# PLL.net
KiCad netlist of a schematic drawn in Altium Designer
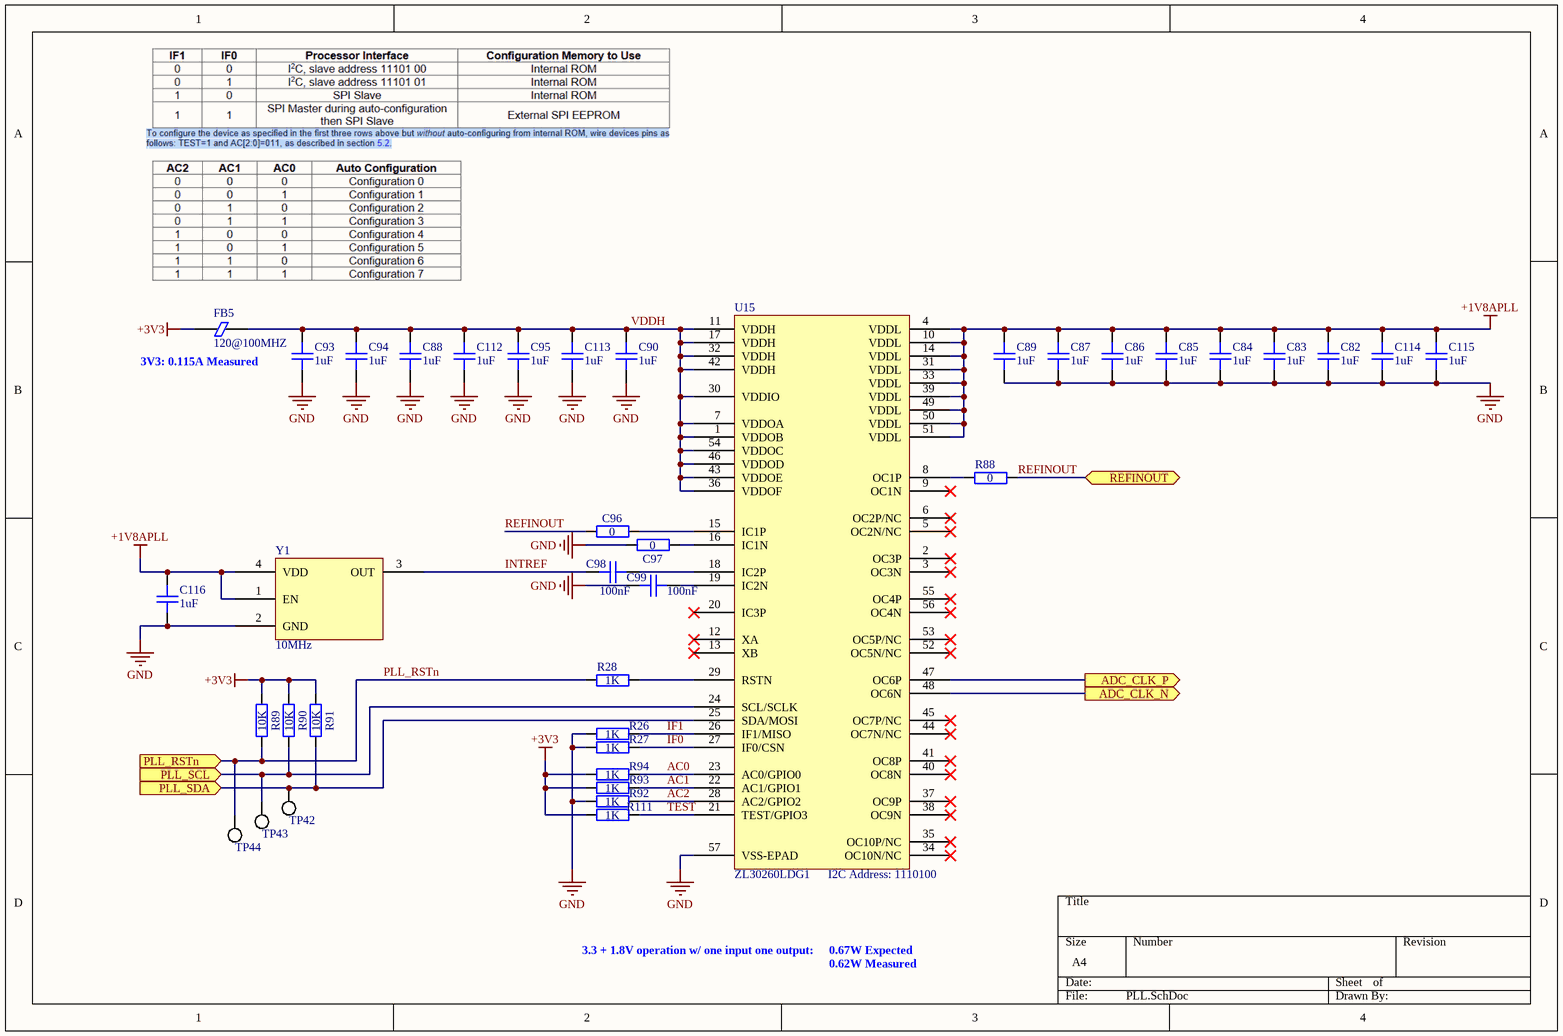
[diagram p0: PLL.SchDoc]

(export (version "E")
  (design (tool "Eeschema 10.0.6"))
  (components
    (comp (ref "C82")
      (value "1uF")
      (footprint "GEN_C_0402")
      (libsource (lib "DSO") (part "CAP 1uF 25V X5R 0402"))
    )
    (comp (ref "C83")
      (value "1uF")
      (footprint "GEN_C_0402")
      (libsource (lib "DSO") (part "CAP 1uF 25V X5R 0402"))
    )
    (comp (ref "C84")
      (value "1uF")
      (footprint "GEN_C_0402")
      (libsource (lib "DSO") (part "CAP 1uF 25V X5R 0402"))
    )
    (comp (ref "C85")
      (value "1uF")
      (footprint "GEN_C_0402")
      (libsource (lib "DSO") (part "CAP 1uF 25V X5R 0402"))
    )
    (comp (ref "C86")
      (value "1uF")
      (footprint "GEN_C_0402")
      (libsource (lib "DSO") (part "CAP 1uF 25V X5R 0402"))
    )
    (comp (ref "C87")
      (value "1uF")
      (footprint "GEN_C_0402")
      (libsource (lib "DSO") (part "CAP 1uF 25V X5R 0402"))
    )
    (comp (ref "C88")
      (value "1uF")
      (footprint "GEN_C_0402")
      (libsource (lib "DSO") (part "CAP 1uF 25V X5R 0402"))
    )
    (comp (ref "C89")
      (value "1uF")
      (footprint "GEN_C_0402")
      (libsource (lib "DSO") (part "CAP 1uF 25V X5R 0402"))
    )
    (comp (ref "C90")
      (value "1uF")
      (footprint "GEN_C_0402")
      (libsource (lib "DSO") (part "CAP 1uF 25V X5R 0402"))
    )
    (comp (ref "C93")
      (value "1uF")
      (footprint "GEN_C_0402")
      (libsource (lib "DSO") (part "CAP 1uF 25V X5R 0402"))
    )
    (comp (ref "C94")
      (value "1uF")
      (footprint "GEN_C_0402")
      (libsource (lib "DSO") (part "CAP 1uF 25V X5R 0402"))
    )
    (comp (ref "C95")
      (value "1uF")
      (footprint "GEN_C_0402")
      (libsource (lib "DSO") (part "CAP 1uF 25V X5R 0402"))
    )
    (comp (ref "C96")
      (value "0")
      (footprint "GEN_R_0402")
      (fields
        (field (name "MANUFACTURER") "Yageo")
        (field (name "MANUFACTURER PART NUMBER") "RC0402JR-070RL")
      )
      (libsource (lib "DSO") (part "RES 0 OHM 1/16W 0402"))
    )
    (comp (ref "C97")
      (value "0")
      (footprint "GEN_R_0402")
      (fields
        (field (name "MANUFACTURER") "Yageo")
        (field (name "MANUFACTURER PART NUMBER") "RC0402JR-070RL")
      )
      (libsource (lib "DSO") (part "RES 0 OHM 1/16W 0402"))
    )
    (comp (ref "C98")
      (value "100nF")
      (footprint "GEN_C_0402")
      (libsource (lib "DSO") (part "CAP 100nF 16V X7R 0402"))
    )
    (comp (ref "C99")
      (value "100nF")
      (footprint "GEN_C_0402")
      (libsource (lib "DSO") (part "CAP 100nF 16V X7R 0402"))
    )
    (comp (ref "C112")
      (value "1uF")
      (footprint "GEN_C_0402")
      (libsource (lib "DSO") (part "CAP 1uF 25V X5R 0402"))
    )
    (comp (ref "C113")
      (value "1uF")
      (footprint "GEN_C_0402")
      (libsource (lib "DSO") (part "CAP 1uF 25V X5R 0402"))
    )
    (comp (ref "C114")
      (value "1uF")
      (footprint "GEN_C_0402")
      (libsource (lib "DSO") (part "CAP 1uF 25V X5R 0402"))
    )
    (comp (ref "C115")
      (value "1uF")
      (footprint "GEN_C_0402")
      (libsource (lib "DSO") (part "CAP 1uF 25V X5R 0402"))
    )
    (comp (ref "C116")
      (value "1uF")
      (footprint "GEN_C_0402")
      (libsource (lib "DSO") (part "CAP 1uF 25V X5R 0402"))
    )
    (comp (ref "FB5")
      (value "120@100MHZ")
      (footprint "GEN_R_0402")
      (libsource (lib "DSO") (part "FERRITE BEAD 120 OHM 0402"))
    )
    (comp (ref "R26")
      (value "1K")
      (footprint "GEN_R_0402")
      (fields
        (field (name "TOLERANCE") "1%")
        (field (name "MANUFACTURER") "Yageo")
        (field (name "HOUSE PART NUMBER") "R-1K-0402-1%-001")
      )
      (libsource (lib "DSO") (part "RES 1K OHM 1% 1/10W 0402"))
    )
    (comp (ref "R27")
      (value "1K")
      (footprint "GEN_R_0402")
      (fields
        (field (name "TOLERANCE") "1%")
        (field (name "MANUFACTURER") "Yageo")
        (field (name "HOUSE PART NUMBER") "R-1K-0402-1%-001")
      )
      (libsource (lib "DSO") (part "RES 1K OHM 1% 1/10W 0402"))
    )
    (comp (ref "R28")
      (value "1K")
      (footprint "GEN_R_0402")
      (fields
        (field (name "TOLERANCE") "1%")
        (field (name "MANUFACTURER") "Yageo")
        (field (name "HOUSE PART NUMBER") "R-1K-0402-1%-001")
      )
      (libsource (lib "") (part "RES 1K OHM 1% 1/10W 0402_1"))
    )
    (comp (ref "R88")
      (value "0")
      (footprint "GEN_R_0402")
      (libsource (lib "") (part "RES 0 OHM 1/16W 0402_1"))
    )
    (comp (ref "R89")
      (value "10K")
      (footprint "GEN_R_0402")
      (fields (field (name "TOLERANCE") "1%"))
      (libsource (lib "DSO") (part "RES 10K OHM 1% 1/10W 0402"))
    )
    (comp (ref "R90")
      (value "10K")
      (footprint "GEN_R_0402")
      (fields (field (name "TOLERANCE") "1%"))
      (libsource (lib "DSO") (part "RES 10K OHM 1% 1/10W 0402"))
    )
    (comp (ref "R91")
      (value "10K")
      (footprint "GEN_R_0402")
      (fields (field (name "TOLERANCE") "1%"))
      (libsource (lib "DSO") (part "RES 10K OHM 1% 1/10W 0402"))
    )
    (comp (ref "R92")
      (value "1K")
      (footprint "GEN_R_0402")
      (fields
        (field (name "TOLERANCE") "1%")
        (field (name "MANUFACTURER") "Yageo")
        (field (name "HOUSE PART NUMBER") "R-1K-0402-1%-001")
      )
      (libsource (lib "DSO") (part "RES 1K OHM 1% 1/10W 0402"))
    )
    (comp (ref "R93")
      (value "1K")
      (footprint "GEN_R_0402")
      (fields
        (field (name "TOLERANCE") "1%")
        (field (name "MANUFACTURER") "Yageo")
        (field (name "HOUSE PART NUMBER") "R-1K-0402-1%-001")
      )
      (libsource (lib "DSO") (part "RES 1K OHM 1% 1/10W 0402"))
    )
    (comp (ref "R94")
      (value "1K")
      (footprint "GEN_R_0402")
      (fields
        (field (name "TOLERANCE") "1%")
        (field (name "MANUFACTURER") "Yageo")
        (field (name "HOUSE PART NUMBER") "R-1K-0402-1%-001")
      )
      (libsource (lib "DSO") (part "RES 1K OHM 1% 1/10W 0402"))
    )
    (comp (ref "R111")
      (value "1K")
      (footprint "GEN_R_0402")
      (fields
        (field (name "TOLERANCE") "1%")
        (field (name "MANUFACTURER") "Yageo")
        (field (name "HOUSE PART NUMBER") "R-1K-0402-1%-001")
      )
      (libsource (lib "DSO") (part "RES 1K OHM 1% 1/10W 0402"))
    )
    (comp (ref "TP42") (value "PCB") (footprint "GEN_TP_PCB") (libsource (lib "DSO") (part "TP PCB 1mm")))
    (comp (ref "TP43") (value "PCB") (footprint "GEN_TP_PCB") (libsource (lib "DSO") (part "TP PCB 1mm")))
    (comp (ref "TP44") (value "PCB") (footprint "GEN_TP_PCB") (libsource (lib "DSO") (part "TP PCB 1mm")))
    (comp (ref "U15")
      (value "ZL30260LDG1")
      (footprint "MC_QFN56_ZL30260")
      (fields (field (name "MANUFACTURER") "Microchip"))
      (libsource (lib "DSO") (part "IC CLK GEN ZL30260LDG1"))
    )
    (comp (ref "Y1")
      (value "10MHz")
      (footprint "ECS_TXO-3225")
      (libsource (lib "DSO") (part "OSC 10MHz ECS-TXO-3225MV"))
    )
  )
  (nets
    (net (code "1") (name "+1V8APLL") (class "Default")
      (node (ref "C114") (pin "1") (pinfunction "1_1") (pintype "passive"))
      (node (ref "C115") (pin "1") (pinfunction "1_1") (pintype "passive"))
      (node (ref "C116") (pin "1") (pinfunction "1_1") (pintype "passive"))
      (node (ref "C82") (pin "1") (pinfunction "1_1") (pintype "passive"))
      (node (ref "C83") (pin "1") (pinfunction "1_1") (pintype "passive"))
      (node (ref "C84") (pin "1") (pinfunction "1_1") (pintype "passive"))
      (node (ref "C85") (pin "1") (pinfunction "1_1") (pintype "passive"))
      (node (ref "C86") (pin "1") (pinfunction "1_1") (pintype "passive"))
      (node (ref "C87") (pin "1") (pinfunction "1_1") (pintype "passive"))
      (node (ref "C89") (pin "1") (pinfunction "1_1") (pintype "passive"))
      (node (ref "U15") (pin "10") (pinfunction "VDDL_10") (pintype "passive"))
      (node (ref "U15") (pin "14") (pinfunction "VDDL_14") (pintype "passive"))
      (node (ref "U15") (pin "31") (pinfunction "VDDL_31") (pintype "passive"))
      (node (ref "U15") (pin "33") (pinfunction "VDDL_33") (pintype "passive"))
      (node (ref "U15") (pin "39") (pinfunction "VDDL_39") (pintype "passive"))
      (node (ref "U15") (pin "4") (pinfunction "VDDL_4") (pintype "passive"))
      (node (ref "U15") (pin "49") (pinfunction "VDDL_49") (pintype "passive"))
      (node (ref "U15") (pin "50") (pinfunction "VDDL_50") (pintype "passive"))
      (node (ref "U15") (pin "51") (pinfunction "VDDL_51") (pintype "passive"))
      (node (ref "Y1") (pin "1") (pinfunction "EN_1") (pintype "passive"))
      (node (ref "Y1") (pin "4") (pinfunction "VDD_4") (pintype "power_in"))
    )
    (net (code "2") (name "+3V3") (class "Default")
      (node (ref "FB5") (pin "1") (pinfunction "1_1") (pintype "passive"))
      (node (ref "R111") (pin "1") (pinfunction "1_1") (pintype "passive"))
      (node (ref "R89") (pin "2") (pinfunction "2_2") (pintype "passive"))
      (node (ref "R90") (pin "2") (pinfunction "2_2") (pintype "passive"))
      (node (ref "R91") (pin "2") (pinfunction "2_2") (pintype "passive"))
      (node (ref "R93") (pin "1") (pinfunction "1_1") (pintype "passive"))
      (node (ref "R94") (pin "1") (pinfunction "1_1") (pintype "passive"))
    )
    (net (code "3") (name "/AC0") (class "Default")
      (node (ref "R94") (pin "2") (pinfunction "2_2") (pintype "passive"))
      (node (ref "U15") (pin "23") (pinfunction "AC0/GPIO0_23") (pintype "passive"))
    )
    (net (code "4") (name "/AC1") (class "Default")
      (node (ref "R93") (pin "2") (pinfunction "2_2") (pintype "passive"))
      (node (ref "U15") (pin "22") (pinfunction "AC1/GPIO1_22") (pintype "passive"))
    )
    (net (code "5") (name "/AC2") (class "Default")
      (node (ref "R92") (pin "2") (pinfunction "2_2") (pintype "passive"))
      (node (ref "U15") (pin "28") (pinfunction "AC2/GPIO2_28") (pintype "passive"))
    )
    (net (code "6") (name "/ADC_CLK_N") (class "Default")
      (node (ref "U15") (pin "48") (pinfunction "OC6N_48") (pintype "passive"))
    )
    (net (code "7") (name "/ADC_CLK_P") (class "Default")
      (node (ref "U15") (pin "47") (pinfunction "OC6P_47") (pintype "passive"))
    )
    (net (code "8") (name "/IF0") (class "Default")
      (node (ref "R27") (pin "2") (pinfunction "2_2") (pintype "passive"))
      (node (ref "U15") (pin "27") (pinfunction "IF0/CSN_27") (pintype "passive"))
    )
    (net (code "9") (name "/IF1") (class "Default")
      (node (ref "R26") (pin "2") (pinfunction "2_2") (pintype "passive"))
      (node (ref "U15") (pin "26") (pinfunction "IF1/MISO_26") (pintype "passive"))
    )
    (net (code "10") (name "/INTREF") (class "Default")
      (node (ref "C98") (pin "2") (pinfunction "2_2") (pintype "passive"))
      (node (ref "Y1") (pin "3") (pinfunction "OUT_3") (pintype "passive"))
    )
    (net (code "11") (name "/PLL_RSTn") (class "Default")
      (node (ref "R28") (pin "2") (pinfunction "2_2") (pintype "passive"))
      (node (ref "R89") (pin "1") (pinfunction "1_1") (pintype "passive"))
      (node (ref "TP44") (pin "1") (pinfunction "1_1") (pintype "passive"))
    )
    (net (code "12") (name "/PLL_SCL") (class "Default")
      (node (ref "R90") (pin "1") (pinfunction "1_1") (pintype "passive"))
      (node (ref "TP43") (pin "1") (pinfunction "1_1") (pintype "passive"))
      (node (ref "U15") (pin "24") (pinfunction "SCL/SCLK_24") (pintype "passive"))
    )
    (net (code "13") (name "/PLL_SDA") (class "Default")
      (node (ref "R91") (pin "1") (pinfunction "1_1") (pintype "passive"))
      (node (ref "TP42") (pin "1") (pinfunction "1_1") (pintype "passive"))
      (node (ref "U15") (pin "25") (pinfunction "SDA/MOSI_25") (pintype "passive"))
    )
    (net (code "14") (name "/REFINOUT") (class "Default")
      (node (ref "C96") (pin "2") (pinfunction "2_2") (pintype "passive"))
      (node (ref "R88") (pin "2") (pinfunction "2_2") (pintype "passive"))
    )
    (net (code "15") (name "/TEST") (class "Default")
      (node (ref "R111") (pin "2") (pinfunction "2_2") (pintype "passive"))
      (node (ref "U15") (pin "21") (pinfunction "TEST/GPIO3_21") (pintype "passive"))
    )
    (net (code "16") (name "/VDDH") (class "Default")
      (node (ref "C112") (pin "1") (pinfunction "1_1") (pintype "passive"))
      (node (ref "C113") (pin "1") (pinfunction "1_1") (pintype "passive"))
      (node (ref "C88") (pin "1") (pinfunction "1_1") (pintype "passive"))
      (node (ref "C90") (pin "1") (pinfunction "1_1") (pintype "passive"))
      (node (ref "C93") (pin "1") (pinfunction "1_1") (pintype "passive"))
      (node (ref "C94") (pin "1") (pinfunction "1_1") (pintype "passive"))
      (node (ref "C95") (pin "1") (pinfunction "1_1") (pintype "passive"))
      (node (ref "FB5") (pin "2") (pinfunction "2_2") (pintype "passive"))
      (node (ref "U15") (pin "1") (pinfunction "VDDOB_1") (pintype "passive"))
      (node (ref "U15") (pin "11") (pinfunction "VDDH_11") (pintype "passive"))
      (node (ref "U15") (pin "17") (pinfunction "VDDH_17") (pintype "passive"))
      (node (ref "U15") (pin "30") (pinfunction "VDDIO_30") (pintype "passive"))
      (node (ref "U15") (pin "32") (pinfunction "VDDH_32") (pintype "passive"))
      (node (ref "U15") (pin "36") (pinfunction "VDDOF_36") (pintype "passive"))
      (node (ref "U15") (pin "42") (pinfunction "VDDH_42") (pintype "passive"))
      (node (ref "U15") (pin "43") (pinfunction "VDDOE_43") (pintype "passive"))
      (node (ref "U15") (pin "46") (pinfunction "VDDOD_46") (pintype "passive"))
      (node (ref "U15") (pin "54") (pinfunction "VDDOC_54") (pintype "passive"))
      (node (ref "U15") (pin "7") (pinfunction "VDDOA_7") (pintype "passive"))
    )
    (net (code "17") (name "GND") (class "Default")
      (node (ref "C112") (pin "2") (pinfunction "2_2") (pintype "passive"))
      (node (ref "C113") (pin "2") (pinfunction "2_2") (pintype "passive"))
      (node (ref "C114") (pin "2") (pinfunction "2_2") (pintype "passive"))
      (node (ref "C115") (pin "2") (pinfunction "2_2") (pintype "passive"))
      (node (ref "C116") (pin "2") (pinfunction "2_2") (pintype "passive"))
      (node (ref "C82") (pin "2") (pinfunction "2_2") (pintype "passive"))
      (node (ref "C83") (pin "2") (pinfunction "2_2") (pintype "passive"))
      (node (ref "C84") (pin "2") (pinfunction "2_2") (pintype "passive"))
      (node (ref "C85") (pin "2") (pinfunction "2_2") (pintype "passive"))
      (node (ref "C86") (pin "2") (pinfunction "2_2") (pintype "passive"))
      (node (ref "C87") (pin "2") (pinfunction "2_2") (pintype "passive"))
      (node (ref "C88") (pin "2") (pinfunction "2_2") (pintype "passive"))
      (node (ref "C89") (pin "2") (pinfunction "2_2") (pintype "passive"))
      (node (ref "C90") (pin "2") (pinfunction "2_2") (pintype "passive"))
      (node (ref "C93") (pin "2") (pinfunction "2_2") (pintype "passive"))
      (node (ref "C94") (pin "2") (pinfunction "2_2") (pintype "passive"))
      (node (ref "C95") (pin "2") (pinfunction "2_2") (pintype "passive"))
      (node (ref "C97") (pin "2") (pinfunction "2_2") (pintype "passive"))
      (node (ref "C99") (pin "2") (pinfunction "2_2") (pintype "passive"))
      (node (ref "R26") (pin "1") (pinfunction "1_1") (pintype "passive"))
      (node (ref "R27") (pin "1") (pinfunction "1_1") (pintype "passive"))
      (node (ref "R92") (pin "1") (pinfunction "1_1") (pintype "passive"))
      (node (ref "U15") (pin "57") (pinfunction "VSS-EPAD_57") (pintype "passive"))
      (node (ref "Y1") (pin "2") (pinfunction "GND_2") (pintype "power_in"))
    )
    (net (code "18") (name "Net-(U15-IC1N)") (class "Default")
      (node (ref "C97") (pin "1") (pinfunction "1_1") (pintype "passive"))
      (node (ref "U15") (pin "16") (pinfunction "IC1N_16") (pintype "passive"))
    )
    (net (code "19") (name "Net-(U15-IC1P)") (class "Default")
      (node (ref "C96") (pin "1") (pinfunction "1_1") (pintype "passive"))
      (node (ref "U15") (pin "15") (pinfunction "IC1P_15") (pintype "passive"))
    )
    (net (code "20") (name "Net-(U15-IC2N)") (class "Default")
      (node (ref "C99") (pin "1") (pinfunction "1_1") (pintype "passive"))
      (node (ref "U15") (pin "19") (pinfunction "IC2N_19") (pintype "passive"))
    )
    (net (code "21") (name "Net-(U15-IC2P)") (class "Default")
      (node (ref "C98") (pin "1") (pinfunction "1_1") (pintype "passive"))
      (node (ref "U15") (pin "18") (pinfunction "IC2P_18") (pintype "passive"))
    )
    (net (code "22") (name "Net-(U15-OC1P)") (class "Default")
      (node (ref "R88") (pin "1") (pinfunction "1_1") (pintype "passive"))
      (node (ref "U15") (pin "8") (pinfunction "OC1P_8") (pintype "passive"))
    )
    (net (code "23") (name "Net-(U15-RSTN)") (class "Default")
      (node (ref "R28") (pin "1") (pinfunction "1_1") (pintype "passive"))
      (node (ref "U15") (pin "29") (pinfunction "RSTN_29") (pintype "passive"))
    )
    (net (code "24") (name "unconnected-(U15-IC3P-Pad20)") (class "Default")
      (node (ref "U15") (pin "20") (pinfunction "IC3P_20") (pintype "passive+no_connect"))
    )
    (net (code "25") (name "unconnected-(U15-OC1N-Pad9)") (class "Default")
      (node (ref "U15") (pin "9") (pinfunction "OC1N_9") (pintype "passive+no_connect"))
    )
    (net (code "26") (name "unconnected-(U15-OC2N{slash}NC-Pad5)") (class "Default")
      (node (ref "U15") (pin "5") (pinfunction "OC2N/NC_5") (pintype "passive+no_connect"))
    )
    (net (code "27") (name "unconnected-(U15-OC2P{slash}NC-Pad6)") (class "Default")
      (node (ref "U15") (pin "6") (pinfunction "OC2P/NC_6") (pintype "passive+no_connect"))
    )
    (net (code "28") (name "unconnected-(U15-OC3N-Pad3)") (class "Default")
      (node (ref "U15") (pin "3") (pinfunction "OC3N_3") (pintype "passive+no_connect"))
    )
    (net (code "29") (name "unconnected-(U15-OC3P-Pad2)") (class "Default")
      (node (ref "U15") (pin "2") (pinfunction "OC3P_2") (pintype "passive+no_connect"))
    )
    (net (code "30") (name "unconnected-(U15-OC4N-Pad56)") (class "Default")
      (node (ref "U15") (pin "56") (pinfunction "OC4N_56") (pintype "passive+no_connect"))
    )
    (net (code "31") (name "unconnected-(U15-OC4P-Pad55)") (class "Default")
      (node (ref "U15") (pin "55") (pinfunction "OC4P_55") (pintype "passive+no_connect"))
    )
    (net (code "32") (name "unconnected-(U15-OC5N{slash}NC-Pad52)") (class "Default")
      (node (ref "U15") (pin "52") (pinfunction "OC5N/NC_52") (pintype "passive+no_connect"))
    )
    (net (code "33") (name "unconnected-(U15-OC5P{slash}NC-Pad53)") (class "Default")
      (node (ref "U15") (pin "53") (pinfunction "OC5P/NC_53") (pintype "passive+no_connect"))
    )
    (net (code "34") (name "unconnected-(U15-OC7N{slash}NC-Pad44)") (class "Default")
      (node (ref "U15") (pin "44") (pinfunction "OC7N/NC_44") (pintype "passive+no_connect"))
    )
    (net (code "35") (name "unconnected-(U15-OC7P{slash}NC-Pad45)") (class "Default")
      (node (ref "U15") (pin "45") (pinfunction "OC7P/NC_45") (pintype "passive+no_connect"))
    )
    (net (code "36") (name "unconnected-(U15-OC8N-Pad40)") (class "Default")
      (node (ref "U15") (pin "40") (pinfunction "OC8N_40") (pintype "passive+no_connect"))
    )
    (net (code "37") (name "unconnected-(U15-OC8P-Pad41)") (class "Default")
      (node (ref "U15") (pin "41") (pinfunction "OC8P_41") (pintype "passive+no_connect"))
    )
    (net (code "38") (name "unconnected-(U15-OC9N-Pad38)") (class "Default")
      (node (ref "U15") (pin "38") (pinfunction "OC9N_38") (pintype "passive+no_connect"))
    )
    (net (code "39") (name "unconnected-(U15-OC9P-Pad37)") (class "Default")
      (node (ref "U15") (pin "37") (pinfunction "OC9P_37") (pintype "passive+no_connect"))
    )
    (net (code "40") (name "unconnected-(U15-OC10N{slash}NC-Pad34)") (class "Default")
      (node (ref "U15") (pin "34") (pinfunction "OC10N/NC_34") (pintype "passive+no_connect"))
    )
    (net (code "41") (name "unconnected-(U15-OC10P{slash}NC-Pad35)") (class "Default")
      (node (ref "U15") (pin "35") (pinfunction "OC10P/NC_35") (pintype "passive+no_connect"))
    )
    (net (code "42") (name "unconnected-(U15-XA-Pad12)") (class "Default")
      (node (ref "U15") (pin "12") (pinfunction "XA_12") (pintype "passive+no_connect"))
    )
    (net (code "43") (name "unconnected-(U15-XB-Pad13)") (class "Default")
      (node (ref "U15") (pin "13") (pinfunction "XB_13") (pintype "passive+no_connect"))
    )
  )
)
